# RESISTORS-BOARD.net
KiCad netlist of a schematic drawn in Altium Designer
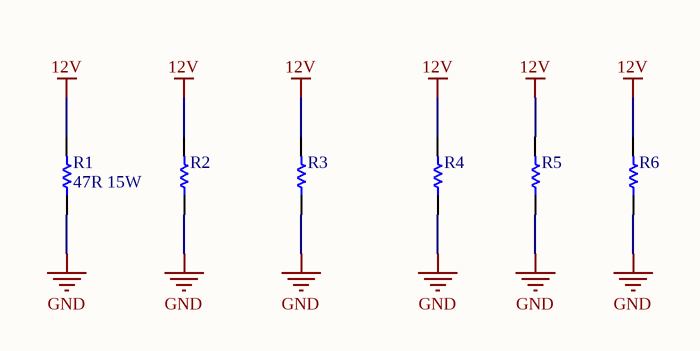
[diagram p0: RESISTORS-BOARD.SchDoc]

(export (version "E")
  (design (tool "Eeschema 10.0.6"))
  (components
    (comp (ref "R1")
      (value "47R 15W")
      (footprint "RES-CERAMICA-15W")
      (description "Resistencia Ceramica 15E 5% 15W SE15 RES.CEM")
      (libsource (lib "Libreria-Resistencias") (part "Resistencia Ceramica 15E 5% 15W SE15 RES.CEM"))
    )
    (comp (ref "R2")
      (value "Resistencia Ceramica 15E 5% 15W SE15 RES.CEM")
      (footprint "RES-CERAMICA-15W")
      (libsource (lib "Libreria-Resistencias") (part "Resistencia Ceramica 15E 5% 15W SE15 RES.CEM"))
    )
    (comp (ref "R3")
      (value "Resistencia Ceramica 15E 5% 15W SE15 RES.CEM")
      (footprint "RES-CERAMICA-15W")
      (libsource (lib "Libreria-Resistencias") (part "Resistencia Ceramica 15E 5% 15W SE15 RES.CEM"))
    )
    (comp (ref "R4")
      (value "Resistencia Ceramica 15E 5% 15W SE15 RES.CEM")
      (footprint "RES-CERAMICA-15W")
      (libsource (lib "Libreria-Resistencias") (part "Resistencia Ceramica 15E 5% 15W SE15 RES.CEM"))
    )
    (comp (ref "R5")
      (value "Resistencia Ceramica 15E 5% 15W SE15 RES.CEM")
      (footprint "RES-CERAMICA-15W")
      (libsource (lib "Libreria-Resistencias") (part "Resistencia Ceramica 15E 5% 15W SE15 RES.CEM"))
    )
    (comp (ref "R6")
      (value "Resistencia Ceramica 15E 5% 15W SE15 RES.CEM")
      (footprint "RES-CERAMICA-15W")
      (libsource (lib "Libreria-Resistencias") (part "Resistencia Ceramica 15E 5% 15W SE15 RES.CEM"))
    )
  )
  (nets
    (net (code "1") (name "12V") (class "Default")
      (node (ref "R1") (pin "2") (pinfunction "2_2") (pintype "passive"))
      (node (ref "R2") (pin "2") (pinfunction "2_2") (pintype "passive"))
      (node (ref "R3") (pin "2") (pinfunction "2_2") (pintype "passive"))
      (node (ref "R4") (pin "2") (pinfunction "2_2") (pintype "passive"))
      (node (ref "R5") (pin "2") (pinfunction "2_2") (pintype "passive"))
      (node (ref "R6") (pin "2") (pinfunction "2_2") (pintype "passive"))
    )
    (net (code "2") (name "GND") (class "Default")
      (node (ref "R1") (pin "1") (pinfunction "1_1") (pintype "passive"))
      (node (ref "R2") (pin "1") (pinfunction "1_1") (pintype "passive"))
      (node (ref "R3") (pin "1") (pinfunction "1_1") (pintype "passive"))
      (node (ref "R4") (pin "1") (pinfunction "1_1") (pintype "passive"))
      (node (ref "R5") (pin "1") (pinfunction "1_1") (pintype "passive"))
      (node (ref "R6") (pin "1") (pinfunction "1_1") (pintype "passive"))
    )
  )
)
